# AIWAC_A33_LVDS07_20181114.net
KiCad netlist of a schematic drawn in Altium Designer
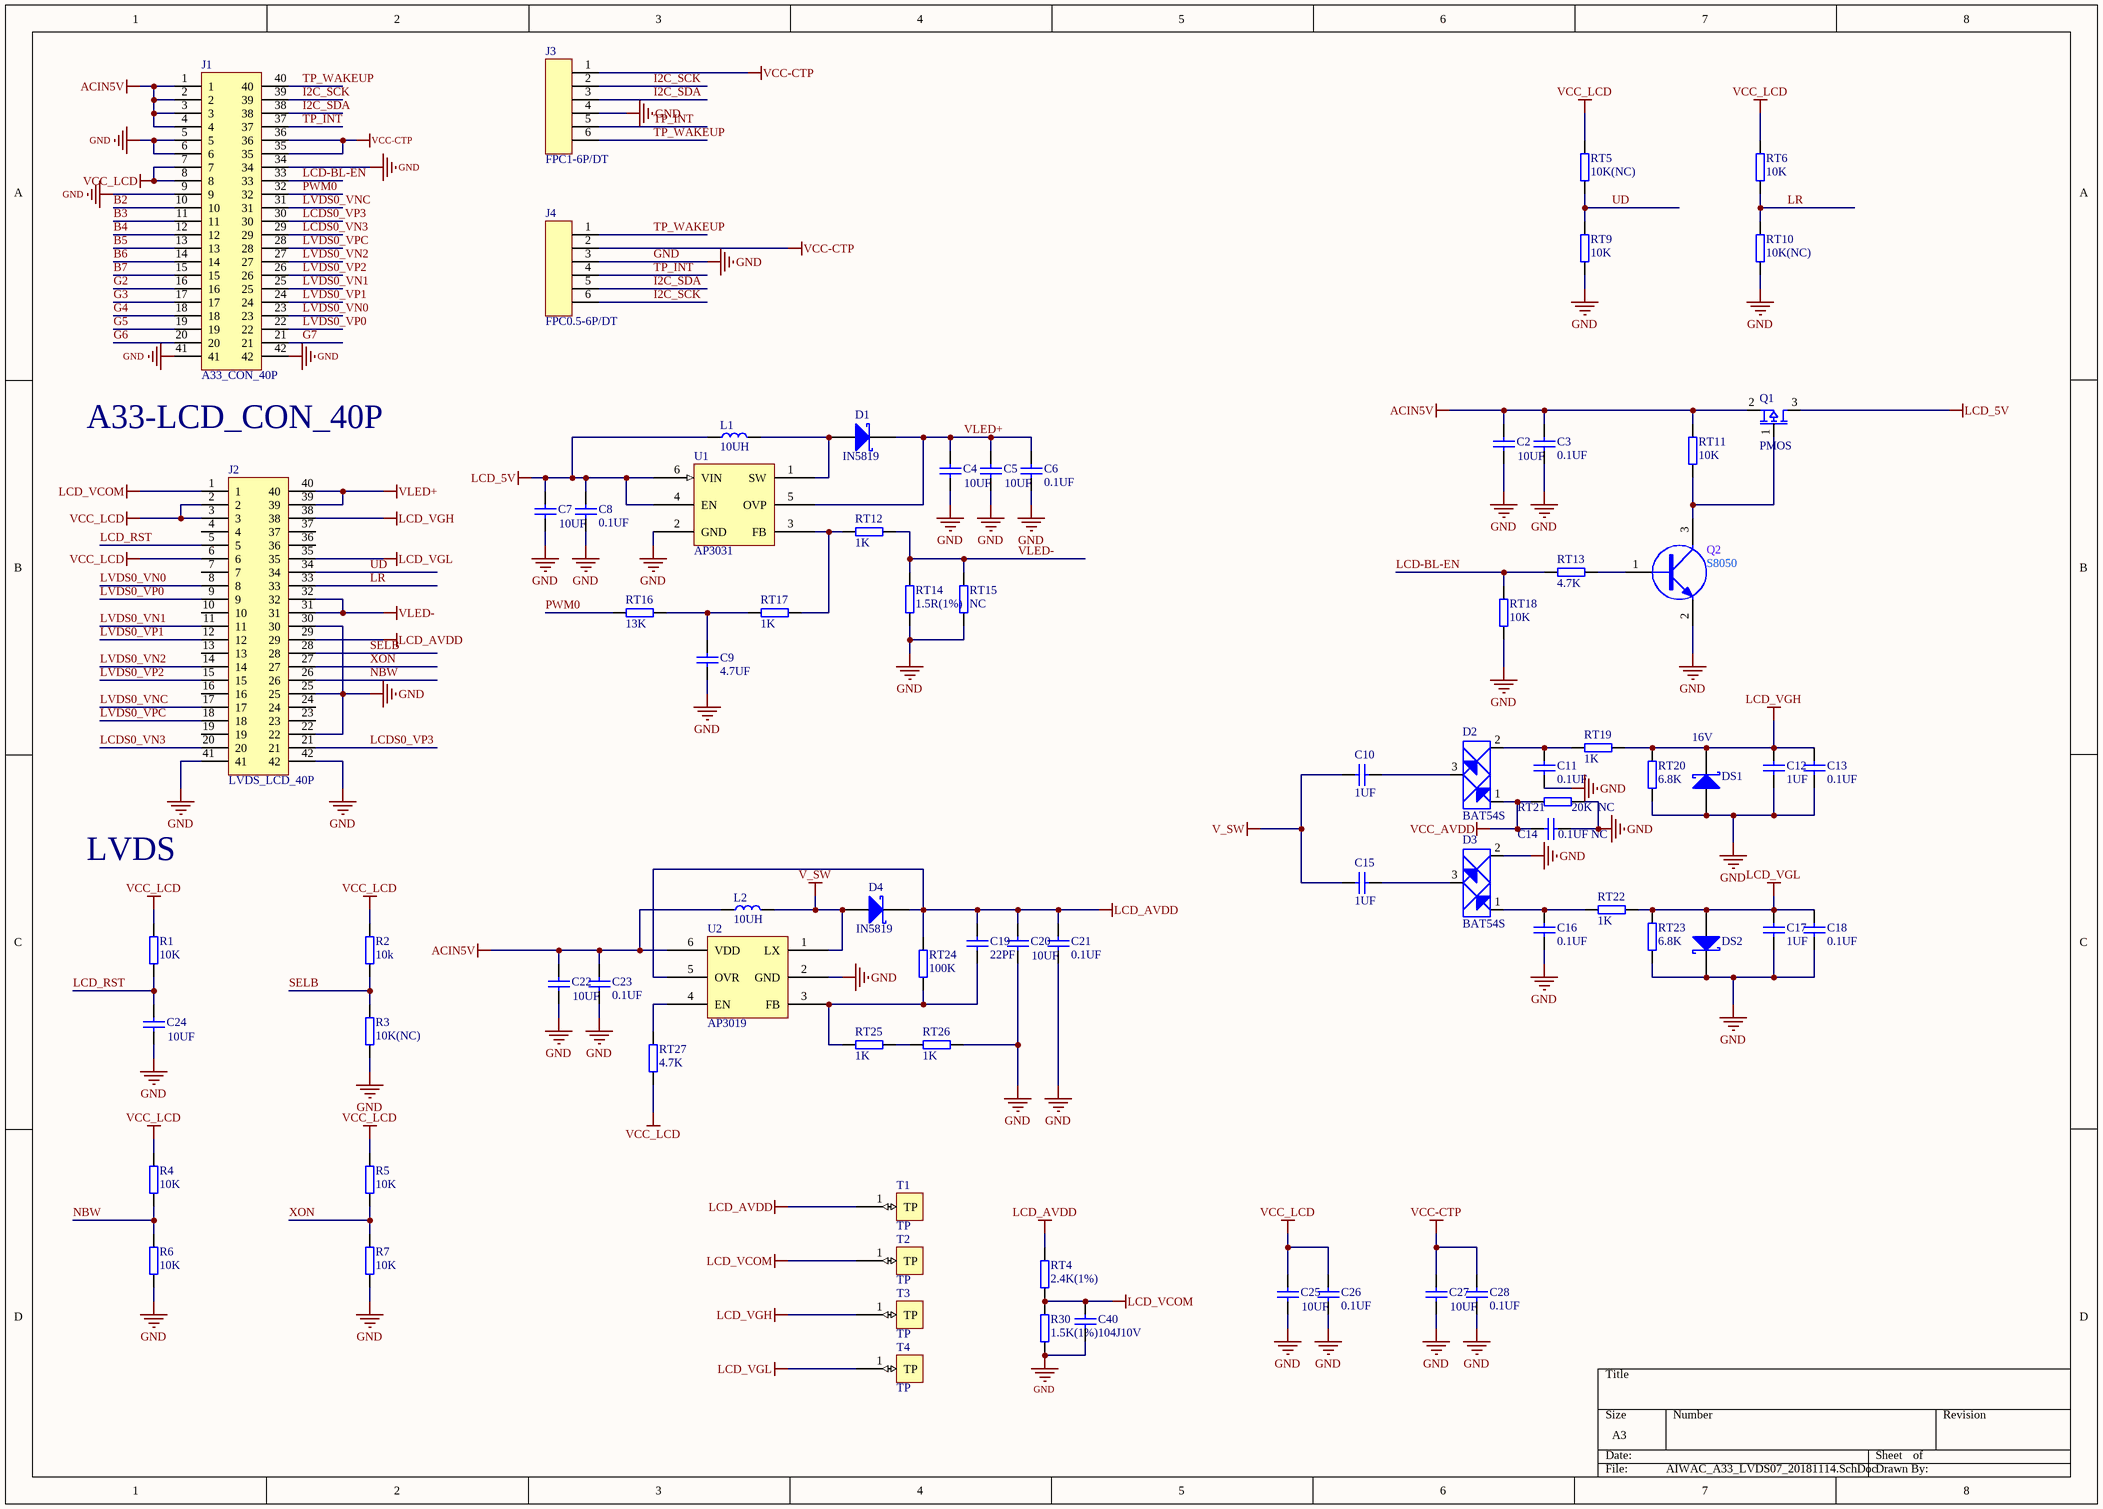
[diagram p0: AIWAC_A33_LVDS07_20181114.SchDoc]

(export (version "E")
  (design (tool "Eeschema 10.0.6"))
  (components
    (comp (ref "C2")
      (value "10UF")
      (footprint "C0805")
      (description "贴片电容-陶瓷")
      (libsource (lib "Capacitor") (part "C0805X7R-226K25V"))
    )
    (comp (ref "C3")
      (value "0.1UF")
      (footprint "C0402")
      (description "贴片电容-陶瓷")
      (libsource (lib "Capacitor") (part "C0402X7R-104J10V"))
    )
    (comp (ref "C4")
      (value "10UF")
      (footprint "C0805")
      (description "贴片电容-陶瓷")
      (libsource (lib "Capacitor") (part "C0805X7R-226K25V"))
    )
    (comp (ref "C5")
      (value "10UF")
      (footprint "C0805")
      (description "贴片电容-陶瓷")
      (libsource (lib "Capacitor") (part "C0805X7R-226K25V"))
    )
    (comp (ref "C6")
      (value "0.1UF")
      (footprint "C0402")
      (description "贴片电容-陶瓷")
      (libsource (lib "Capacitor") (part "C0402X7R-104J10V"))
    )
    (comp (ref "C7")
      (value "10UF")
      (footprint "C0805")
      (description "贴片电容-陶瓷")
      (libsource (lib "Capacitor") (part "C0805X7R-226K25V"))
    )
    (comp (ref "C8")
      (value "0.1UF")
      (footprint "C0402")
      (description "贴片电容-陶瓷")
      (libsource (lib "Capacitor") (part "C0402X7R-104J10V"))
    )
    (comp (ref "C9")
      (value "4.7UF")
      (footprint "C0603")
      (description "贴片电容-陶瓷")
      (libsource (lib "Capacitor") (part "C0603X7R-330J25V"))
    )
    (comp (ref "C10")
      (value "1UF")
      (footprint "C0603")
      (description "贴片电容-陶瓷")
      (libsource (lib "Capacitor") (part "C0603X7R-330J25V"))
    )
    (comp (ref "C11")
      (value "0.1UF")
      (footprint "C0402")
      (description "贴片电容-陶瓷")
      (libsource (lib "Capacitor") (part "C0402X7R-104J10V"))
    )
    (comp (ref "C12")
      (value "1UF")
      (footprint "C0603")
      (description "贴片电容-陶瓷")
      (libsource (lib "Capacitor") (part "C0603X7R-330J25V"))
    )
    (comp (ref "C13")
      (value "0.1UF")
      (footprint "C0402")
      (description "贴片电容-陶瓷")
      (libsource (lib "Capacitor") (part "C0402X7R-104J10V"))
    )
    (comp (ref "C14")
      (value "0.1UF NC")
      (footprint "C0603")
      (description "贴片电容-陶瓷")
      (libsource (lib "Capacitor") (part "C0603X7R-330J25V"))
    )
    (comp (ref "C15")
      (value "1UF")
      (footprint "C0603")
      (description "贴片电容-陶瓷")
      (libsource (lib "Capacitor") (part "C0603X7R-330J25V"))
    )
    (comp (ref "C16")
      (value "0.1UF")
      (footprint "C0402")
      (description "贴片电容-陶瓷")
      (libsource (lib "Capacitor") (part "C0402X7R-104J10V"))
    )
    (comp (ref "C17")
      (value "1UF")
      (footprint "C0603")
      (description "贴片电容-陶瓷")
      (libsource (lib "Capacitor") (part "C0603X7R-330J25V"))
    )
    (comp (ref "C18")
      (value "0.1UF")
      (footprint "C0402")
      (description "贴片电容-陶瓷")
      (libsource (lib "Capacitor") (part "C0402X7R-104J10V"))
    )
    (comp (ref "C19")
      (value "22PF")
      (footprint "C0402")
      (description "贴片电容-陶瓷")
      (libsource (lib "Capacitor") (part "C0402X7R-104J10V"))
    )
    (comp (ref "C20")
      (value "10UF")
      (footprint "C0805")
      (description "贴片电容-陶瓷")
      (libsource (lib "Capacitor") (part "C0805X7R-226K25V"))
    )
    (comp (ref "C21")
      (value "0.1UF")
      (footprint "C0402")
      (description "贴片电容-陶瓷")
      (libsource (lib "Capacitor") (part "C0402X7R-104J10V"))
    )
    (comp (ref "C22")
      (value "10UF")
      (footprint "C0805")
      (description "贴片电容-陶瓷")
      (libsource (lib "Capacitor") (part "C0805X7R-226K25V"))
    )
    (comp (ref "C23")
      (value "0.1UF")
      (footprint "C0402")
      (description "贴片电容-陶瓷")
      (libsource (lib "Capacitor") (part "C0402X7R-104J10V"))
    )
    (comp (ref "C24")
      (value "10UF")
      (footprint "C0805")
      (description "贴片电容-陶瓷")
      (libsource (lib "Capacitor") (part "C0805X7R-226K25V"))
    )
    (comp (ref "C25")
      (value "10UF")
      (footprint "C0805")
      (description "贴片电容-陶瓷")
      (libsource (lib "Capacitor") (part "C0805X7R-226K25V"))
    )
    (comp (ref "C26")
      (value "0.1UF")
      (footprint "C0402")
      (description "贴片电容-陶瓷")
      (libsource (lib "Capacitor") (part "C0402X7R-104J10V"))
    )
    (comp (ref "C27")
      (value "10UF")
      (footprint "C0805")
      (description "贴片电容-陶瓷")
      (libsource (lib "Capacitor") (part "C0805X7R-226K25V"))
    )
    (comp (ref "C28")
      (value "0.1UF")
      (footprint "C0402")
      (description "贴片电容-陶瓷")
      (libsource (lib "Capacitor") (part "C0402X7R-104J10V"))
    )
    (comp (ref "C40")
      (value "104J10V")
      (footprint "C0402")
      (description "贴片电容-陶瓷")
      (libsource (lib "Capacitor") (part "C0402X7R-104J10V"))
    )
    (comp (ref "D1")
      (value "IN5819")
      (footprint "SMB")
      (description "Schottky Diode")
      (fields (field (name "PUBLISHER") "Altium Limited"))
      (libsource (lib "XU-GENARAL SCH") (part "D Schottky"))
    )
    (comp (ref "D2")
      (value "BAT54S")
      (footprint "U-SOT-23-3")
      (libsource (lib "AIWAC-bolsterV01") (part "BAT54S"))
    )
    (comp (ref "D3")
      (value "BAT54S")
      (footprint "U-SOT-23-3")
      (libsource (lib "AIWAC-bolsterV01") (part "BAT54S"))
    )
    (comp (ref "D4")
      (value "IN5819")
      (footprint "SMB")
      (description "Schottky Diode")
      (fields (field (name "PUBLISHER") "Altium Limited"))
      (libsource (lib "XU-GENARAL SCH") (part "D Schottky"))
    )
    (comp (ref "DS1")
      (value "16V")
      (footprint "SMB")
      (description "Schottky Diode")
      (fields (field (name "PUBLISHER") "Altium Limited"))
      (libsource (lib "XU-GENARAL SCH") (part "D Schottky"))
    )
    (comp (ref "DS2")
      (value "7.5V")
      (footprint "SMB")
      (description "Schottky Diode")
      (fields (field (name "PUBLISHER") "Altium Limited"))
      (libsource (lib "XU-GENARAL SCH") (part "D Schottky"))
    )
    (comp (ref "J1")
      (value "A33_CON_40P")
      (footprint "LCD P40")
      (description "LCD_40P")
      (libsource (lib "Connector") (part "LCD_40P"))
    )
    (comp (ref "J2")
      (value "LVDS_LCD_40P")
      (footprint "FPC-59240HU010R")
      (description "LCD_40P")
      (libsource (lib "Connector") (part "LCD_40P"))
    )
    (comp (ref "J3")
      (value "FPC1-6P/DT")
      (footprint "FPC0.5-6P/DT")
      (description "FPC端子")
      (libsource (lib "Sheye-Connector") (part "J-FPC0.5-6P/DT"))
    )
    (comp (ref "J4")
      (value "FPC0.5-6P/DT")
      (footprint "FPC0.5-6P/DT")
      (description "FPC端子")
      (libsource (lib "Sheye-Connector") (part "J-FPC0.5-6P/DT"))
    )
    (comp (ref "L1")
      (value "10UH")
      (footprint "D1206")
      (description "贴片电感-屏蔽")
      (libsource (lib "AIWAC-bolsterV01") (part "3.3uH"))
    )
    (comp (ref "L2")
      (value "10UH")
      (footprint "D1206")
      (description "贴片电感-屏蔽")
      (libsource (lib "AIWAC-bolsterV01") (part "3.3uH"))
    )
    (comp (ref "Q1")
      (value "PMOS")
      (footprint "U-SOT-23-3")
      (description "贴片MOSFET管")
      (libsource (lib "AIWAC-bolsterV01") (part "PMOS"))
    )
    (comp (ref "Q2")
      (value "S8050")
      (footprint "U-SOT-23-3")
      (description "三极管")
      (libsource (lib "标准通用原理图库") (part "SS8050 TO-23"))
    )
    (comp (ref "R1")
      (value "10K")
      (footprint "R0402")
      (description "贴片电阻-通用")
      (libsource (lib "Resistor") (part "R0402-4.7KF"))
    )
    (comp (ref "R2")
      (value "10k")
      (footprint "R0402")
      (description "贴片电阻-通用")
      (libsource (lib "Resistor") (part "R0402-4.7KF"))
    )
    (comp (ref "R3")
      (value "10K(NC)")
      (footprint "R0402")
      (description "贴片电阻-通用")
      (libsource (lib "Resistor") (part "R0402-4.7KF"))
    )
    (comp (ref "R4")
      (value "10K")
      (footprint "R0402")
      (description "贴片电阻-通用")
      (libsource (lib "Resistor") (part "R0402-4.7KF"))
    )
    (comp (ref "R5")
      (value "10K")
      (footprint "R0402")
      (description "贴片电阻-通用")
      (libsource (lib "Resistor") (part "R0402-4.7KF"))
    )
    (comp (ref "R6")
      (value "10K")
      (footprint "R0402")
      (description "贴片电阻-通用")
      (libsource (lib "Resistor") (part "R0402-4.7KF"))
    )
    (comp (ref "R7")
      (value "10K")
      (footprint "R0402")
      (description "贴片电阻-通用")
      (libsource (lib "Resistor") (part "R0402-4.7KF"))
    )
    (comp (ref "R30")
      (value "1.5K(1%)")
      (footprint "R0603")
      (description "贴片电阻-通用")
      (libsource (lib "Resistor") (part "R0603-10KF"))
    )
    (comp (ref "RT4")
      (value "2.4K(1%)")
      (footprint "XU-GENARAL PCB :0402")
      (description "贴片电阻-通用")
      (libsource (lib "Resistor") (part "R0603-10KF"))
    )
    (comp (ref "RT5")
      (value "10K(NC)")
      (footprint "XU-GENARAL PCB :0402")
      (description "贴片电阻-通用")
      (libsource (lib "Resistor") (part "R0603-10KF"))
    )
    (comp (ref "RT6")
      (value "10K")
      (footprint "XU-GENARAL PCB :0402")
      (description "贴片电阻-通用")
      (libsource (lib "Resistor") (part "R0603-10KF"))
    )
    (comp (ref "RT9")
      (value "10K")
      (footprint "XU-GENARAL PCB :0402")
      (description "贴片电阻-通用")
      (libsource (lib "Resistor") (part "R0603-10KF"))
    )
    (comp (ref "RT10")
      (value "10K(NC)")
      (footprint "XU-GENARAL PCB :0402")
      (description "贴片电阻-通用")
      (libsource (lib "Resistor") (part "R0603-10KF"))
    )
    (comp (ref "RT11")
      (value "10K")
      (footprint "XU-GENARAL PCB :0402")
      (description "贴片电阻-通用")
      (libsource (lib "Resistor") (part "R0603-10KF"))
    )
    (comp (ref "RT12")
      (value "1K")
      (footprint "XU-GENARAL PCB :0402")
      (description "贴片电阻-通用")
      (libsource (lib "Resistor") (part "R0603-10KF"))
    )
    (comp (ref "RT13")
      (value "4.7K")
      (footprint "XU-GENARAL PCB :0402")
      (description "贴片电阻-通用")
      (libsource (lib "Resistor") (part "R0603-10KF"))
    )
    (comp (ref "RT14")
      (value "1.5R(1%)")
      (footprint "XU-GENARAL PCB :0402")
      (description "贴片电阻-通用")
      (libsource (lib "Resistor") (part "R0603-10KF"))
    )
    (comp (ref "RT15")
      (value "NC")
      (footprint "XU-GENARAL PCB :0402")
      (description "贴片电阻-通用")
      (libsource (lib "Resistor") (part "R0603-10KF"))
    )
    (comp (ref "RT16")
      (value "13K")
      (footprint "XU-GENARAL PCB :0402")
      (description "贴片电阻-通用")
      (libsource (lib "Resistor") (part "R0603-10KF"))
    )
    (comp (ref "RT17")
      (value "1K")
      (footprint "XU-GENARAL PCB :0402")
      (description "贴片电阻-通用")
      (libsource (lib "Resistor") (part "R0603-10KF"))
    )
    (comp (ref "RT18")
      (value "10K")
      (footprint "XU-GENARAL PCB :0402")
      (description "贴片电阻-通用")
      (libsource (lib "Resistor") (part "R0603-10KF"))
    )
    (comp (ref "RT19")
      (value "1K")
      (footprint "XU-GENARAL PCB :0402")
      (description "贴片电阻-通用")
      (libsource (lib "Resistor") (part "R0603-10KF"))
    )
    (comp (ref "RT20")
      (value "6.8K")
      (footprint "XU-GENARAL PCB :0402")
      (description "贴片电阻-通用")
      (libsource (lib "Resistor") (part "R0603-10KF"))
    )
    (comp (ref "RT21")
      (value "20K  NC")
      (footprint "XU-GENARAL PCB :0402")
      (description "贴片电阻-通用")
      (libsource (lib "Resistor") (part "R0603-10KF"))
    )
    (comp (ref "RT22")
      (value "1K")
      (footprint "XU-GENARAL PCB :0402")
      (description "贴片电阻-通用")
      (libsource (lib "Resistor") (part "R0603-10KF"))
    )
    (comp (ref "RT23")
      (value "6.8K")
      (footprint "XU-GENARAL PCB :0402")
      (description "贴片电阻-通用")
      (libsource (lib "Resistor") (part "R0603-10KF"))
    )
    (comp (ref "RT24")
      (value "100K")
      (footprint "XU-GENARAL PCB :0402")
      (description "贴片电阻-通用")
      (libsource (lib "Resistor") (part "R0603-10KF"))
    )
    (comp (ref "RT25")
      (value "1K")
      (footprint "XU-GENARAL PCB :0402")
      (description "贴片电阻-通用")
      (libsource (lib "Resistor") (part "R0603-10KF"))
    )
    (comp (ref "RT26")
      (value "1K")
      (footprint "XU-GENARAL PCB :0402")
      (description "贴片电阻-通用")
      (libsource (lib "Resistor") (part "R0603-10KF"))
    )
    (comp (ref "RT27")
      (value "4.7K")
      (footprint "XU-GENARAL PCB :0402")
      (description "贴片电阻-通用")
      (libsource (lib "Resistor") (part "R0603-10KF"))
    )
    (comp (ref "T1") (value "TP") (footprint "PAD") (libsource (lib "AIWAC-bolsterV01") (part "TP")))
    (comp (ref "T2") (value "TP") (footprint "PAD") (libsource (lib "AIWAC-bolsterV01") (part "TP")))
    (comp (ref "T3") (value "TP") (footprint "PAD") (libsource (lib "AIWAC-bolsterV01") (part "TP")))
    (comp (ref "T4") (value "TP") (footprint "PAD") (libsource (lib "AIWAC-bolsterV01") (part "TP")))
    (comp (ref "U1")
      (value "AP3031")
      (footprint "U-SOT-23-6")
      (libsource (lib "AIWAC-bolsterV01") (part "AP3031"))
    )
    (comp (ref "U2")
      (value "AP3019")
      (footprint "U-SOT-23-6")
      (libsource (lib "AIWAC-bolsterV01") (part "AP3019"))
    )
  )
  (nets
    (net (code "1") (name "/B2") (class "Default")
      (node (ref "J1") (pin "10") (pinfunction "10_10") (pintype "passive"))
    )
    (net (code "2") (name "/B3") (class "Default")
      (node (ref "J1") (pin "11") (pinfunction "11_11") (pintype "passive"))
    )
    (net (code "3") (name "/B4") (class "Default")
      (node (ref "J1") (pin "12") (pinfunction "12_12") (pintype "passive"))
    )
    (net (code "4") (name "/B5") (class "Default")
      (node (ref "J1") (pin "13") (pinfunction "13_13") (pintype "passive"))
    )
    (net (code "5") (name "/B6") (class "Default")
      (node (ref "J1") (pin "14") (pinfunction "14_14") (pintype "passive"))
    )
    (net (code "6") (name "/B7") (class "Default")
      (node (ref "J1") (pin "15") (pinfunction "15_15") (pintype "passive"))
    )
    (net (code "7") (name "/G2") (class "Default")
      (node (ref "J1") (pin "16") (pinfunction "16_16") (pintype "passive"))
    )
    (net (code "8") (name "/G3") (class "Default")
      (node (ref "J1") (pin "17") (pinfunction "17_17") (pintype "passive"))
    )
    (net (code "9") (name "/G4") (class "Default")
      (node (ref "J1") (pin "18") (pinfunction "18_18") (pintype "passive"))
    )
    (net (code "10") (name "/G5") (class "Default")
      (node (ref "J1") (pin "19") (pinfunction "19_19") (pintype "passive"))
    )
    (net (code "11") (name "/G6") (class "Default")
      (node (ref "J1") (pin "20") (pinfunction "20_20") (pintype "passive"))
    )
    (net (code "12") (name "/G7") (class "Default")
      (node (ref "J1") (pin "21") (pinfunction "21_21") (pintype "passive"))
    )
    (net (code "13") (name "/I2C_SCK") (class "Default")
      (node (ref "J1") (pin "39") (pinfunction "39_39") (pintype "passive"))
      (node (ref "J3") (pin "2") (pinfunction "2_2") (pintype "passive"))
      (node (ref "J4") (pin "6") (pinfunction "6_6") (pintype "passive"))
    )
    (net (code "14") (name "/I2C_SDA") (class "Default")
      (node (ref "J1") (pin "38") (pinfunction "38_38") (pintype "passive"))
      (node (ref "J3") (pin "3") (pinfunction "3_3") (pintype "passive"))
      (node (ref "J4") (pin "5") (pinfunction "5_5") (pintype "passive"))
    )
    (net (code "15") (name "/LCD-BL-EN") (class "Default")
      (node (ref "J1") (pin "33") (pinfunction "33_33") (pintype "passive"))
      (node (ref "RT13") (pin "2") (pinfunction "2_2") (pintype "passive"))
      (node (ref "RT18") (pin "1") (pinfunction "1_1") (pintype "passive"))
    )
    (net (code "16") (name "/LCDS0_VN3") (class "Default")
      (node (ref "J1") (pin "29") (pinfunction "29_29") (pintype "passive"))
      (node (ref "J2") (pin "20") (pinfunction "20_20") (pintype "passive"))
    )
    (net (code "17") (name "/LCDS0_VP3") (class "Default")
      (node (ref "J1") (pin "30") (pinfunction "30_30") (pintype "passive"))
      (node (ref "J2") (pin "21") (pinfunction "21_21") (pintype "passive"))
    )
    (net (code "18") (name "/LCD_RST") (class "Default")
      (node (ref "C24") (pin "1") (pinfunction "1_1") (pintype "passive"))
      (node (ref "J2") (pin "5") (pinfunction "5_5") (pintype "passive"))
      (node (ref "R1") (pin "1") (pinfunction "1_1") (pintype "passive"))
    )
    (net (code "19") (name "/LR") (class "Default")
      (node (ref "J2") (pin "33") (pinfunction "33_33") (pintype "passive"))
      (node (ref "RT10") (pin "1") (pinfunction "1_1") (pintype "passive"))
      (node (ref "RT6") (pin "2") (pinfunction "2_2") (pintype "passive"))
    )
    (net (code "20") (name "/LVDS0_VN0") (class "Default")
      (node (ref "J1") (pin "23") (pinfunction "23_23") (pintype "passive"))
      (node (ref "J2") (pin "8") (pinfunction "8_8") (pintype "passive"))
    )
    (net (code "21") (name "/LVDS0_VN1") (class "Default")
      (node (ref "J1") (pin "25") (pinfunction "25_25") (pintype "passive"))
      (node (ref "J2") (pin "11") (pinfunction "11_11") (pintype "passive"))
    )
    (net (code "22") (name "/LVDS0_VN2") (class "Default")
      (node (ref "J1") (pin "27") (pinfunction "27_27") (pintype "passive"))
      (node (ref "J2") (pin "14") (pinfunction "14_14") (pintype "passive"))
    )
    (net (code "23") (name "/LVDS0_VNC") (class "Default")
      (node (ref "J1") (pin "31") (pinfunction "31_31") (pintype "passive"))
      (node (ref "J2") (pin "17") (pinfunction "17_17") (pintype "passive"))
    )
    (net (code "24") (name "/LVDS0_VP0") (class "Default")
      (node (ref "J1") (pin "22") (pinfunction "22_22") (pintype "passive"))
      (node (ref "J2") (pin "9") (pinfunction "9_9") (pintype "passive"))
    )
    (net (code "25") (name "/LVDS0_VP1") (class "Default")
      (node (ref "J1") (pin "24") (pinfunction "24_24") (pintype "passive"))
      (node (ref "J2") (pin "12") (pinfunction "12_12") (pintype "passive"))
    )
    (net (code "26") (name "/LVDS0_VP2") (class "Default")
      (node (ref "J1") (pin "26") (pinfunction "26_26") (pintype "passive"))
      (node (ref "J2") (pin "15") (pinfunction "15_15") (pintype "passive"))
    )
    (net (code "27") (name "/LVDS0_VPC") (class "Default")
      (node (ref "J1") (pin "28") (pinfunction "28_28") (pintype "passive"))
      (node (ref "J2") (pin "18") (pinfunction "18_18") (pintype "passive"))
    )
    (net (code "28") (name "/NBW") (class "Default")
      (node (ref "J2") (pin "26") (pinfunction "26_26") (pintype "passive"))
      (node (ref "R4") (pin "1") (pinfunction "1_1") (pintype "passive"))
      (node (ref "R6") (pin "2") (pinfunction "2_2") (pintype "passive"))
    )
    (net (code "29") (name "/PWM0") (class "Default")
      (node (ref "J1") (pin "32") (pinfunction "32_32") (pintype "passive"))
      (node (ref "RT16") (pin "2") (pinfunction "2_2") (pintype "passive"))
    )
    (net (code "30") (name "/SELB") (class "Default")
      (node (ref "J2") (pin "28") (pinfunction "28_28") (pintype "passive"))
      (node (ref "R2") (pin "1") (pinfunction "1_1") (pintype "passive"))
      (node (ref "R3") (pin "2") (pinfunction "2_2") (pintype "passive"))
    )
    (net (code "31") (name "/TP_INT") (class "Default")
      (node (ref "J1") (pin "37") (pinfunction "37_37") (pintype "passive"))
      (node (ref "J3") (pin "5") (pinfunction "5_5") (pintype "passive"))
      (node (ref "J4") (pin "4") (pinfunction "4_4") (pintype "passive"))
    )
    (net (code "32") (name "/TP_WAKEUP") (class "Default")
      (node (ref "J1") (pin "40") (pinfunction "40_40") (pintype "passive"))
      (node (ref "J3") (pin "6") (pinfunction "6_6") (pintype "passive"))
      (node (ref "J4") (pin "1") (pinfunction "1_1") (pintype "passive"))
    )
    (net (code "33") (name "/UD") (class "Default")
      (node (ref "J2") (pin "34") (pinfunction "34_34") (pintype "passive"))
      (node (ref "RT5") (pin "2") (pinfunction "2_2") (pintype "passive"))
      (node (ref "RT9") (pin "1") (pinfunction "1_1") (pintype "passive"))
    )
    (net (code "34") (name "/XON") (class "Default")
      (node (ref "J2") (pin "27") (pinfunction "27_27") (pintype "passive"))
      (node (ref "R5") (pin "1") (pinfunction "1_1") (pintype "passive"))
      (node (ref "R7") (pin "2") (pinfunction "2_2") (pintype "passive"))
    )
    (net (code "35") (name "ACIN5V") (class "Default")
      (node (ref "C2") (pin "1") (pinfunction "1_1") (pintype "passive"))
      (node (ref "C22") (pin "1") (pinfunction "1_1") (pintype "passive"))
      (node (ref "C23") (pin "1") (pinfunction "1_1") (pintype "passive"))
      (node (ref "C3") (pin "1") (pinfunction "1_1") (pintype "passive"))
      (node (ref "J1") (pin "1") (pinfunction "1_1") (pintype "passive"))
      (node (ref "J1") (pin "2") (pinfunction "2_2") (pintype "passive"))
      (node (ref "J1") (pin "3") (pinfunction "3_3") (pintype "passive"))
      (node (ref "J1") (pin "4") (pinfunction "4_4") (pintype "passive"))
      (node (ref "L2") (pin "1") (pinfunction "1_1") (pintype "passive"))
      (node (ref "Q1") (pin "2") (pinfunction "2_2") (pintype "passive"))
      (node (ref "RT11") (pin "1") (pinfunction "1_1") (pintype "passive"))
      (node (ref "U2") (pin "6") (pinfunction "VDD_6") (pintype "power_in"))
    )
    (net (code "36") (name "GND") (class "Default")
      (node (ref "C11") (pin "2") (pinfunction "2_2") (pintype "passive"))
      (node (ref "C12") (pin "1") (pinfunction "1_1") (pintype "passive"))
      (node (ref "C13") (pin "2") (pinfunction "2_2") (pintype "passive"))
      (node (ref "C14") (pin "1") (pinfunction "1_1") (pintype "passive"))
      (node (ref "C16") (pin "2") (pinfunction "2_2") (pintype "passive"))
      (node (ref "C17") (pin "1") (pinfunction "1_1") (pintype "passive"))
      (node (ref "C18") (pin "2") (pinfunction "2_2") (pintype "passive"))
      (node (ref "C2") (pin "2") (pinfunction "2_2") (pintype "passive"))
      (node (ref "C20") (pin "2") (pinfunction "2_2") (pintype "passive"))
      (node (ref "C21") (pin "2") (pinfunction "2_2") (pintype "passive"))
      (node (ref "C22") (pin "2") (pinfunction "2_2") (pintype "passive"))
      (node (ref "C23") (pin "2") (pinfunction "2_2") (pintype "passive"))
      (node (ref "C24") (pin "2") (pinfunction "2_2") (pintype "passive"))
      (node (ref "C25") (pin "2") (pinfunction "2_2") (pintype "passive"))
      (node (ref "C26") (pin "2") (pinfunction "2_2") (pintype "passive"))
      (node (ref "C27") (pin "2") (pinfunction "2_2") (pintype "passive"))
      (node (ref "C28") (pin "2") (pinfunction "2_2") (pintype "passive"))
      (node (ref "C3") (pin "2") (pinfunction "2_2") (pintype "passive"))
      (node (ref "C4") (pin "2") (pinfunction "2_2") (pintype "passive"))
      (node (ref "C40") (pin "2") (pinfunction "2_2") (pintype "passive"))
      (node (ref "C5") (pin "2") (pinfunction "2_2") (pintype "passive"))
      (node (ref "C6") (pin "2") (pinfunction "2_2") (pintype "passive"))
      (node (ref "C7") (pin "2") (pinfunction "2_2") (pintype "passive"))
      (node (ref "C8") (pin "2") (pinfunction "2_2") (pintype "passive"))
      (node (ref "C9") (pin "1") (pinfunction "1_1") (pintype "passive"))
      (node (ref "D3") (pin "2") (pinfunction "2_2") (pintype "passive"))
      (node (ref "DS1") (pin "1") (pinfunction "A_1") (pintype "passive"))
      (node (ref "DS2") (pin "2") (pinfunction "K_2") (pintype "passive"))
      (node (ref "J1") (pin "34") (pinfunction "34_34") (pintype "passive"))
      (node (ref "J1") (pin "41") (pinfunction "41_41") (pintype "passive"))
      (node (ref "J1") (pin "42") (pinfunction "42_42") (pintype "passive"))
      (node (ref "J1") (pin "5") (pinfunction "5_5") (pintype "passive"))
      (node (ref "J1") (pin "6") (pinfunction "6_6") (pintype "passive"))
      (node (ref "J1") (pin "9") (pinfunction "9_9") (pintype "passive"))
      (node (ref "J2") (pin "22") (pinfunction "22_22") (pintype "passive"))
      (node (ref "J2") (pin "25") (pinfunction "25_25") (pintype "passive"))
      (node (ref "J2") (pin "30") (pinfunction "30_30") (pintype "passive"))
      (node (ref "J2") (pin "41") (pinfunction "41_41") (pintype "passive"))
      (node (ref "J2") (pin "42") (pinfunction "42_42") (pintype "passive"))
      (node (ref "J3") (pin "4") (pinfunction "4_4") (pintype "passive"))
      (node (ref "J4") (pin "3") (pinfunction "3_3") (pintype "passive"))
      (node (ref "Q2") (pin "2") (pinfunction "E_2") (pintype "passive"))
      (node (ref "R3") (pin "1") (pinfunction "1_1") (pintype "passive"))
      (node (ref "R30") (pin "1") (pinfunction "1_1") (pintype "passive"))
      (node (ref "R6") (pin "1") (pinfunction "1_1") (pintype "passive"))
      (node (ref "R7") (pin "1") (pinfunction "1_1") (pintype "passive"))
      (node (ref "RT10") (pin "2") (pinfunction "2_2") (pintype "passive"))
      (node (ref "RT14") (pin "2") (pinfunction "2_2") (pintype "passive"))
      (node (ref "RT15") (pin "2") (pinfunction "2_2") (pintype "passive"))
      (node (ref "RT18") (pin "2") (pinfunction "2_2") (pintype "passive"))
      (node (ref "RT20") (pin "1") (pinfunction "1_1") (pintype "passive"))
      (node (ref "RT21") (pin "1") (pinfunction "1_1") (pintype "passive"))
      (node (ref "RT23") (pin "1") (pinfunction "1_1") (pintype "passive"))
      (node (ref "RT26") (pin "1") (pinfunction "1_1") (pintype "passive"))
      (node (ref "RT9") (pin "2") (pinfunction "2_2") (pintype "passive"))
      (node (ref "U1") (pin "2") (pinfunction "GND_2") (pintype "power_in"))
      (node (ref "U2") (pin "2") (pinfunction "GND_2") (pintype "power_in"))
    )
    (net (code "37") (name "LCD_5V") (class "Default")
      (node (ref "C7") (pin "1") (pinfunction "1_1") (pintype "passive"))
      (node (ref "C8") (pin "1") (pinfunction "1_1") (pintype "passive"))
      (node (ref "L1") (pin "1") (pinfunction "1_1") (pintype "passive"))
      (node (ref "Q1") (pin "3") (pinfunction "3_3") (pintype "passive"))
      (node (ref "U1") (pin "4") (pinfunction "EN_4") (pintype "passive"))
      (node (ref "U1") (pin "6") (pinfunction "VIN_6") (pintype "input"))
    )
    (net (code "38") (name "LCD_AVDD") (class "Default")
      (node (ref "C19") (pin "1") (pinfunction "1_1") (pintype "passive"))
      (node (ref "C20") (pin "1") (pinfunction "1_1") (pintype "passive"))
      (node (ref "C21") (pin "1") (pinfunction "1_1") (pintype "passive"))
      (node (ref "D4") (pin "2") (pinfunction "K_2") (pintype "passive"))
      (node (ref "J2") (pin "29") (pinfunction "29_29") (pintype "passive"))
      (node (ref "RT24") (pin "1") (pinfunction "1_1") (pintype "passive"))
      (node (ref "RT4") (pin "2") (pinfunction "2_2") (pintype "passive"))
      (node (ref "T1") (pin "1") (pinfunction "TP_1") (pintype "bidirectional"))
      (node (ref "U2") (pin "5") (pinfunction "OVR_5") (pintype "passive"))
    )
    (net (code "39") (name "LCD_VCOM") (class "Default")
      (node (ref "C40") (pin "1") (pinfunction "1_1") (pintype "passive"))
      (node (ref "J2") (pin "1") (pinfunction "1_1") (pintype "passive"))
      (node (ref "R30") (pin "2") (pinfunction "2_2") (pintype "passive"))
      (node (ref "RT4") (pin "1") (pinfunction "1_1") (pintype "passive"))
      (node (ref "T2") (pin "1") (pinfunction "TP_1") (pintype "bidirectional"))
    )
    (net (code "40") (name "LCD_VGH") (class "Default")
      (node (ref "C12") (pin "2") (pinfunction "2_2") (pintype "passive"))
      (node (ref "C13") (pin "1") (pinfunction "1_1") (pintype "passive"))
      (node (ref "DS1") (pin "2") (pinfunction "K_2") (pintype "passive"))
      (node (ref "J2") (pin "38") (pinfunction "38_38") (pintype "passive"))
      (node (ref "RT19") (pin "1") (pinfunction "1_1") (pintype "passive"))
      (node (ref "RT20") (pin "2") (pinfunction "2_2") (pintype "passive"))
      (node (ref "T3") (pin "1") (pinfunction "TP_1") (pintype "bidirectional"))
    )
    (net (code "41") (name "LCD_VGL") (class "Default")
      (node (ref "C17") (pin "2") (pinfunction "2_2") (pintype "passive"))
      (node (ref "C18") (pin "1") (pinfunction "1_1") (pintype "passive"))
      (node (ref "DS2") (pin "1") (pinfunction "A_1") (pintype "passive"))
      (node (ref "J2") (pin "35") (pinfunction "35_35") (pintype "passive"))
      (node (ref "RT22") (pin "1") (pinfunction "1_1") (pintype "passive"))
      (node (ref "RT23") (pin "2") (pinfunction "2_2") (pintype "passive"))
      (node (ref "T4") (pin "1") (pinfunction "TP_1") (pintype "bidirectional"))
    )
    (net (code "42") (name "Net-(C9-Pad2)") (class "Default")
      (node (ref "C9") (pin "2") (pinfunction "2_2") (pintype "passive"))
      (node (ref "RT16") (pin "1") (pinfunction "1_1") (pintype "passive"))
      (node (ref "RT17") (pin "2") (pinfunction "2_2") (pintype "passive"))
    )
    (net (code "43") (name "Net-(C10-Pad1)") (class "Default")
      (node (ref "C10") (pin "1") (pinfunction "1_1") (pintype "passive"))
      (node (ref "D2") (pin "3") (pinfunction "3_3") (pintype "passive"))
    )
    (net (code "44") (name "Net-(C11-Pad1)") (class "Default")
      (node (ref "C11") (pin "1") (pinfunction "1_1") (pintype "passive"))
      (node (ref "D2") (pin "2") (pinfunction "2_2") (pintype "passive"))
      (node (ref "RT19") (pin "2") (pinfunction "2_2") (pintype "passive"))
    )
    (net (code "45") (name "Net-(C15-Pad1)") (class "Default")
      (node (ref "C15") (pin "1") (pinfunction "1_1") (pintype "passive"))
      (node (ref "D3") (pin "3") (pinfunction "3_3") (pintype "passive"))
    )
    (net (code "46") (name "Net-(C16-Pad1)") (class "Default")
      (node (ref "C16") (pin "1") (pinfunction "1_1") (pintype "passive"))
      (node (ref "D3") (pin "1") (pinfunction "1_1") (pintype "passive"))
      (node (ref "RT22") (pin "2") (pinfunction "2_2") (pintype "passive"))
    )
    (net (code "47") (name "Net-(D1-A)") (class "Default")
      (node (ref "D1") (pin "1") (pinfunction "A_1") (pintype "passive"))
      (node (ref "L1") (pin "2") (pinfunction "2_2") (pintype "passive"))
      (node (ref "U1") (pin "1") (pinfunction "SW_1") (pintype "passive"))
    )
    (net (code "48") (name "Net-(Q2-B)") (class "Default")
      (node (ref "Q2") (pin "1") (pinfunction "B_1") (pintype "passive"))
      (node (ref "RT13") (pin "1") (pinfunction "1_1") (pintype "passive"))
    )
    (net (code "49") (name "Net-(Q2-C)") (class "Default")
      (node (ref "Q1") (pin "1") (pinfunction "1_1") (pintype "passive"))
      (node (ref "Q2") (pin "3") (pinfunction "C_3") (pintype "passive"))
      (node (ref "RT11") (pin "2") (pinfunction "2_2") (pintype "passive"))
    )
    (net (code "50") (name "Net-(RT25-Pad1)") (class "Default")
      (node (ref "RT25") (pin "1") (pinfunction "1_1") (pintype "passive"))
      (node (ref "RT26") (pin "2") (pinfunction "2_2") (pintype "passive"))
    )
    (net (code "51") (name "Net-(U1-FB)") (class "Default")
      (node (ref "RT12") (pin "2") (pinfunction "2_2") (pintype "passive"))
      (node (ref "RT17") (pin "1") (pinfunction "1_1") (pintype "passive"))
      (node (ref "U1") (pin "3") (pinfunction "FB_3") (pintype "passive"))
    )
    (net (code "52") (name "Net-(U2-EN)") (class "Default")
      (node (ref "RT27") (pin "1") (pinfunction "1_1") (pintype "passive"))
      (node (ref "U2") (pin "4") (pinfunction "EN_4") (pintype "passive"))
    )
    (net (code "53") (name "Net-(U2-FB)") (class "Default")
      (node (ref "C19") (pin "2") (pinfunction "2_2") (pintype "passive"))
      (node (ref "RT24") (pin "2") (pinfunction "2_2") (pintype "passive"))
      (node (ref "RT25") (pin "2") (pinfunction "2_2") (pintype "passive"))
      (node (ref "U2") (pin "3") (pinfunction "FB_3") (pintype "passive"))
    )
    (net (code "54") (name "VCC-CTP") (class "Default")
      (node (ref "C27") (pin "1") (pinfunction "1_1") (pintype "passive"))
      (node (ref "C28") (pin "1") (pinfunction "1_1") (pintype "passive"))
      (node (ref "J1") (pin "35") (pinfunction "35_35") (pintype "passive"))
      (node (ref "J1") (pin "36") (pinfunction "36_36") (pintype "passive"))
      (node (ref "J3") (pin "1") (pinfunction "1_1") (pintype "passive"))
      (node (ref "J4") (pin "2") (pinfunction "2_2") (pintype "passive"))
    )
    (net (code "55") (name "VCC_AVDD") (class "Default")
      (node (ref "C14") (pin "2") (pinfunction "2_2") (pintype "passive"))
      (node (ref "D2") (pin "1") (pinfunction "1_1") (pintype "passive"))
      (node (ref "RT21") (pin "2") (pinfunction "2_2") (pintype "passive"))
    )
    (net (code "56") (name "VCC_LCD") (class "Default")
      (node (ref "C25") (pin "1") (pinfunction "1_1") (pintype "passive"))
      (node (ref "C26") (pin "1") (pinfunction "1_1") (pintype "passive"))
      (node (ref "J1") (pin "7") (pinfunction "7_7") (pintype "passive"))
      (node (ref "J1") (pin "8") (pinfunction "8_8") (pintype "passive"))
      (node (ref "J2") (pin "2") (pinfunction "2_2") (pintype "passive"))
      (node (ref "J2") (pin "3") (pinfunction "3_3") (pintype "passive"))
      (node (ref "J2") (pin "6") (pinfunction "6_6") (pintype "passive"))
      (node (ref "R1") (pin "2") (pinfunction "2_2") (pintype "passive"))
      (node (ref "R2") (pin "2") (pinfunction "2_2") (pintype "passive"))
      (node (ref "R4") (pin "2") (pinfunction "2_2") (pintype "passive"))
      (node (ref "R5") (pin "2") (pinfunction "2_2") (pintype "passive"))
      (node (ref "RT27") (pin "2") (pinfunction "2_2") (pintype "passive"))
      (node (ref "RT5") (pin "1") (pinfunction "1_1") (pintype "passive"))
      (node (ref "RT6") (pin "1") (pinfunction "1_1") (pintype "passive"))
    )
    (net (code "57") (name "VLED+") (class "Default")
      (node (ref "C4") (pin "1") (pinfunction "1_1") (pintype "passive"))
      (node (ref "C5") (pin "1") (pinfunction "1_1") (pintype "passive"))
      (node (ref "C6") (pin "1") (pinfunction "1_1") (pintype "passive"))
      (node (ref "D1") (pin "2") (pinfunction "K_2") (pintype "passive"))
      (node (ref "J2") (pin "39") (pinfunction "39_39") (pintype "passive"))
      (node (ref "J2") (pin "40") (pinfunction "40_40") (pintype "passive"))
      (node (ref "U1") (pin "5") (pinfunction "OVP_5") (pintype "passive"))
    )
    (net (code "58") (name "VLED-") (class "Default")
      (node (ref "J2") (pin "31") (pinfunction "31_31") (pintype "passive"))
      (node (ref "J2") (pin "32") (pinfunction "32_32") (pintype "passive"))
      (node (ref "RT12") (pin "1") (pinfunction "1_1") (pintype "passive"))
      (node (ref "RT14") (pin "1") (pinfunction "1_1") (pintype "passive"))
      (node (ref "RT15") (pin "1") (pinfunction "1_1") (pintype "passive"))
    )
    (net (code "59") (name "V_SW") (class "Default")
      (node (ref "C10") (pin "2") (pinfunction "2_2") (pintype "passive"))
      (node (ref "C15") (pin "2") (pinfunction "2_2") (pintype "passive"))
      (node (ref "D4") (pin "1") (pinfunction "A_1") (pintype "passive"))
      (node (ref "L2") (pin "2") (pinfunction "2_2") (pintype "passive"))
      (node (ref "U2") (pin "1") (pinfunction "LX_1") (pintype "passive"))
    )
    (net (code "60") (name "unconnected-(J2-Pad4)") (class "Default")
      (node (ref "J2") (pin "4") (pinfunction "4_4") (pintype "passive"))
    )
    (net (code "61") (name "unconnected-(J2-Pad7)") (class "Default")
      (node (ref "J2") (pin "7") (pinfunction "7_7") (pintype "passive"))
    )
    (net (code "62") (name "unconnected-(J2-Pad10)") (class "Default")
      (node (ref "J2") (pin "10") (pinfunction "10_10") (pintype "passive"))
    )
    (net (code "63") (name "unconnected-(J2-Pad13)") (class "Default")
      (node (ref "J2") (pin "13") (pinfunction "13_13") (pintype "passive"))
    )
    (net (code "64") (name "unconnected-(J2-Pad16)") (class "Default")
      (node (ref "J2") (pin "16") (pinfunction "16_16") (pintype "passive"))
    )
    (net (code "65") (name "unconnected-(J2-Pad19)") (class "Default")
      (node (ref "J2") (pin "19") (pinfunction "19_19") (pintype "passive"))
    )
    (net (code "66") (name "unconnected-(J2-Pad23)") (class "Default")
      (node (ref "J2") (pin "23") (pinfunction "23_23") (pintype "passive"))
    )
    (net (code "67") (name "unconnected-(J2-Pad24)") (class "Default")
      (node (ref "J2") (pin "24") (pinfunction "24_24") (pintype "passive"))
    )
    (net (code "68") (name "unconnected-(J2-Pad36)") (class "Default")
      (node (ref "J2") (pin "36") (pinfunction "36_36") (pintype "passive"))
    )
    (net (code "69") (name "unconnected-(J2-Pad37)") (class "Default")
      (node (ref "J2") (pin "37") (pinfunction "37_37") (pintype "passive"))
    )
  )
)
